# solenoid.net
KiCad netlist of a schematic drawn in EAGLE
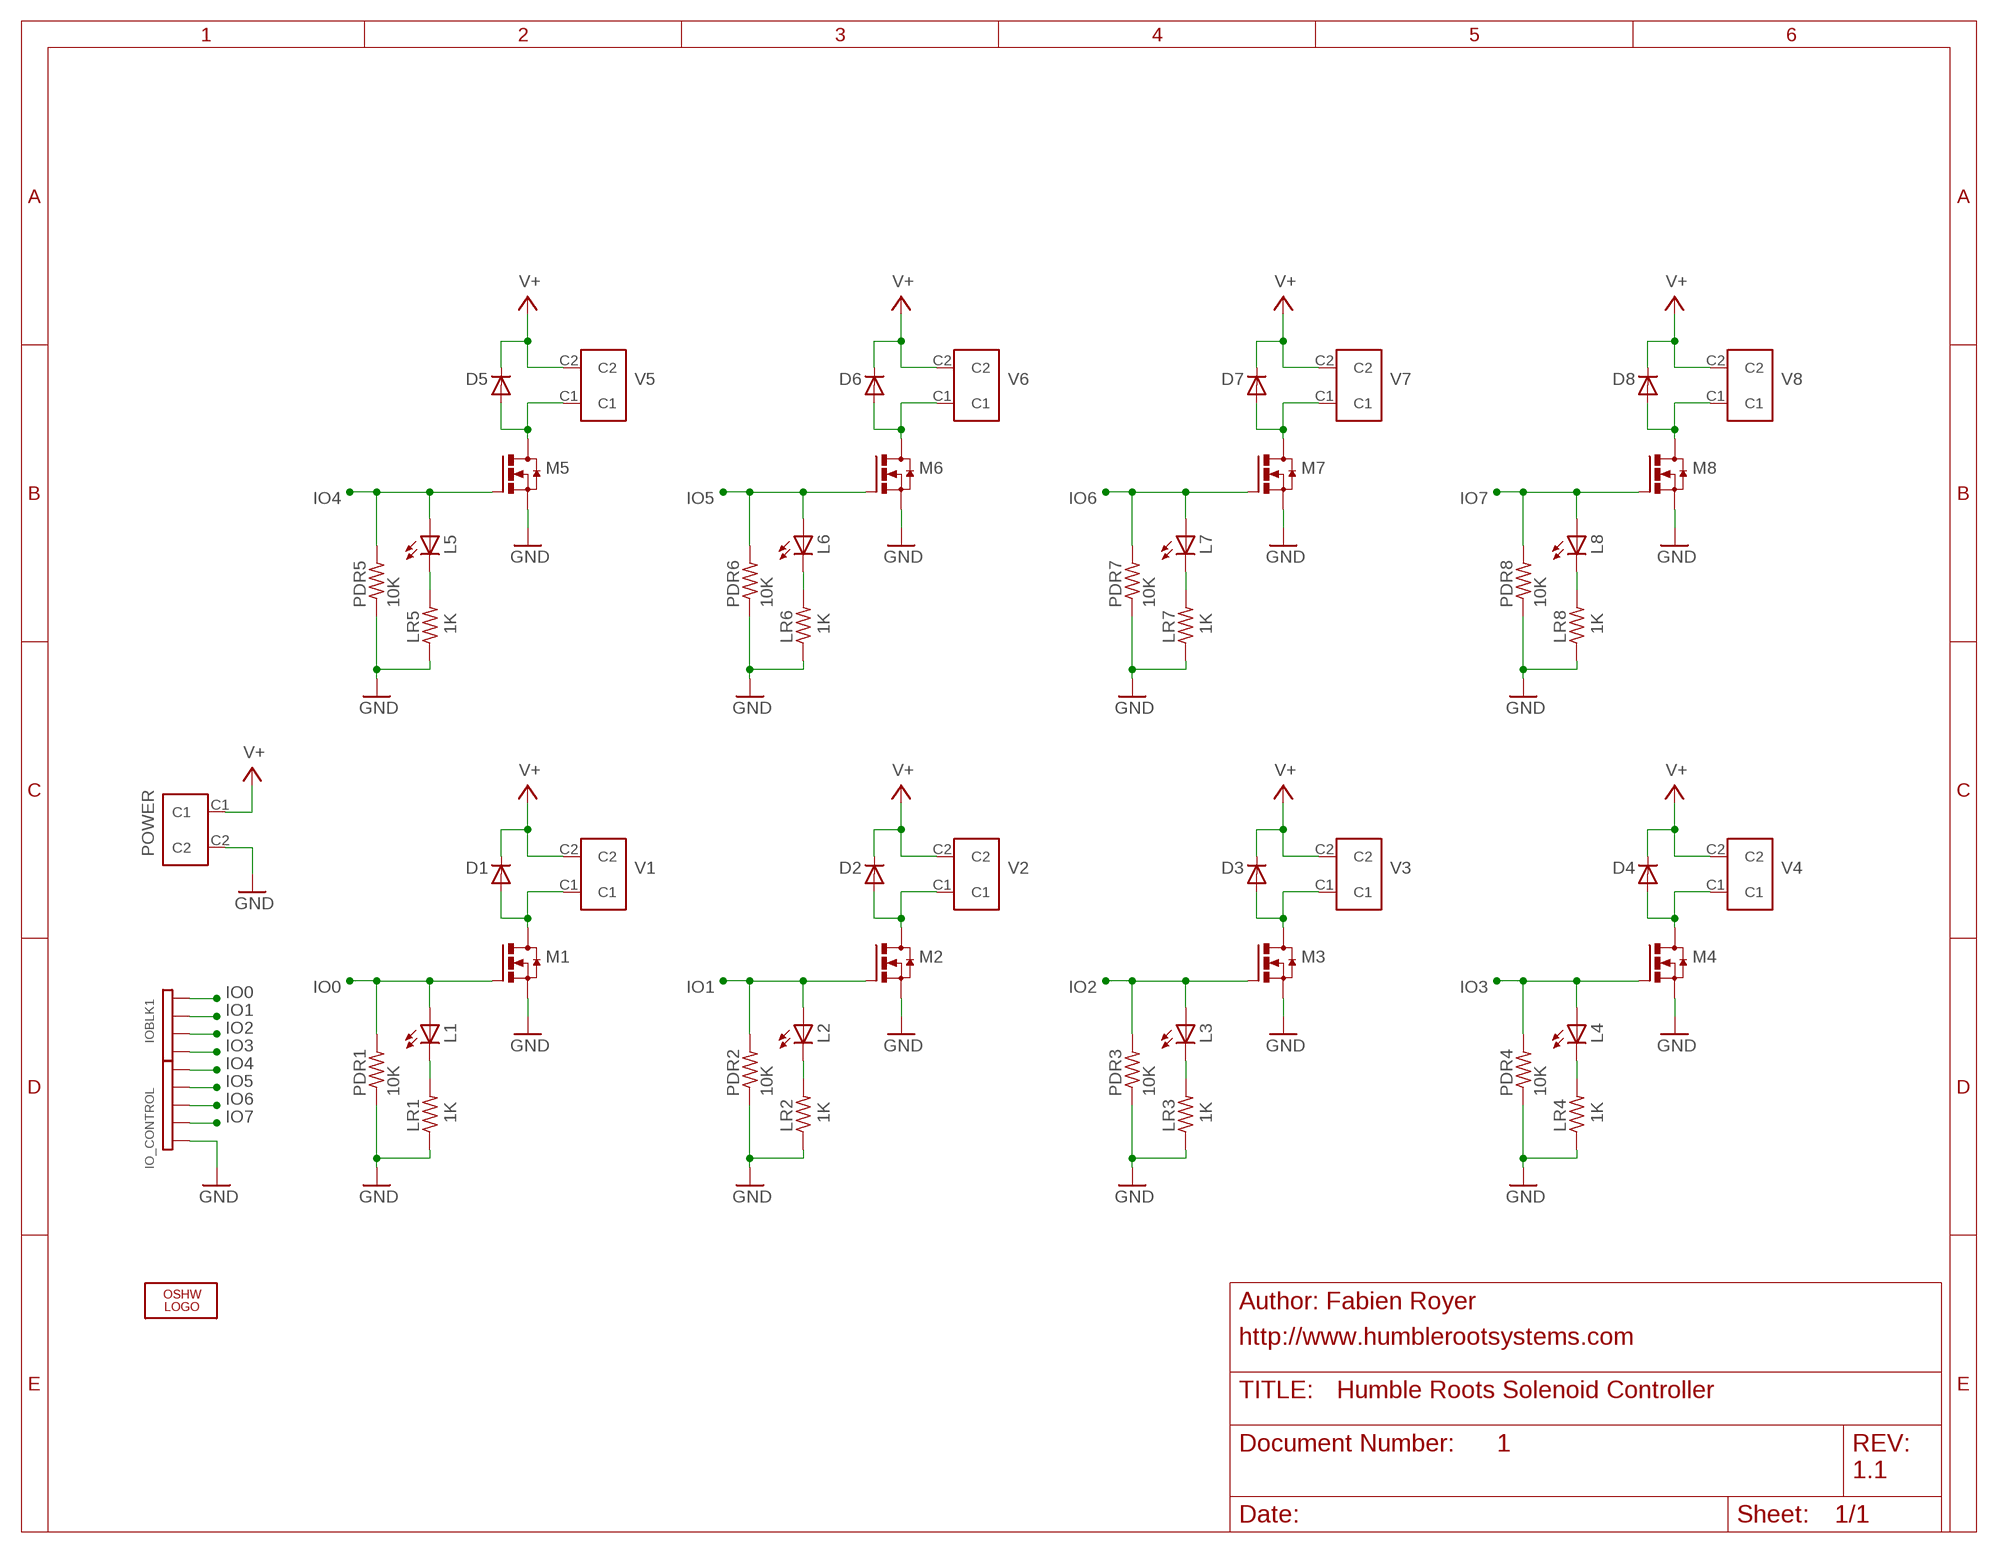
[diagram p0: schematic, sheet 1]

(export (version "E")
  (design (tool "Eeschema 10.0.6"))
  (components
    (comp (ref "D1")
      (value "1N4004")
      (footprint "eagle-import:DO41-10")
      (libsource (lib "eagle-import") (part "1N4004"))
    )
    (comp (ref "D2")
      (value "1N4004")
      (footprint "eagle-import:DO41-10")
      (libsource (lib "eagle-import") (part "1N4004"))
    )
    (comp (ref "D3")
      (value "1N4004")
      (footprint "eagle-import:DO41-10")
      (libsource (lib "eagle-import") (part "1N4004"))
    )
    (comp (ref "D4")
      (value "1N4004")
      (footprint "eagle-import:DO41-10")
      (libsource (lib "eagle-import") (part "1N4004"))
    )
    (comp (ref "D5")
      (value "1N4004")
      (footprint "eagle-import:DO41-10")
      (libsource (lib "eagle-import") (part "1N4004"))
    )
    (comp (ref "D6")
      (value "1N4004")
      (footprint "eagle-import:DO41-10")
      (libsource (lib "eagle-import") (part "1N4004"))
    )
    (comp (ref "D7")
      (value "1N4004")
      (footprint "eagle-import:DO41-10")
      (libsource (lib "eagle-import") (part "1N4004"))
    )
    (comp (ref "D8")
      (value "1N4004")
      (footprint "eagle-import:DO41-10")
      (libsource (lib "eagle-import") (part "1N4004"))
    )
    (comp (ref "IOBLK1")
      (value "PIN_HEADER_4_POSITIONS")
      (footprint "eagle-import:PIN_HEADER_4_POSITIONS")
      (libsource (lib "eagle-import") (part "PIN_HEADER_4_POSITIONS"))
    )
    (comp (ref "IO_CONTROL")
      (value "PIN_HEADER_5_POSITIONS")
      (footprint "eagle-import:PIN_HEADER_5_POSITIONS")
      (libsource (lib "eagle-import") (part "PIN_HEADER_5_POSITIONS"))
    )
    (comp (ref "L1")
      (value "2v 12mA")
      (footprint "eagle-import:LED3MM")
      (libsource (lib "eagle-import") (part "LED3MM"))
    )
    (comp (ref "L2")
      (value "2v 12mA")
      (footprint "eagle-import:LED3MM")
      (libsource (lib "eagle-import") (part "LED3MM"))
    )
    (comp (ref "L3")
      (value "2v 12mA")
      (footprint "eagle-import:LED3MM")
      (libsource (lib "eagle-import") (part "LED3MM"))
    )
    (comp (ref "L4")
      (value "2v 12mA")
      (footprint "eagle-import:LED3MM")
      (libsource (lib "eagle-import") (part "LED3MM"))
    )
    (comp (ref "L5")
      (value "2v 12mA")
      (footprint "eagle-import:LED3MM")
      (libsource (lib "eagle-import") (part "LED3MM"))
    )
    (comp (ref "L6")
      (value "2v 12mA")
      (footprint "eagle-import:LED3MM")
      (libsource (lib "eagle-import") (part "LED3MM"))
    )
    (comp (ref "L7")
      (value "2v 12mA")
      (footprint "eagle-import:LED3MM")
      (libsource (lib "eagle-import") (part "LED3MM"))
    )
    (comp (ref "L8")
      (value "2v 12mA")
      (footprint "eagle-import:LED3MM")
      (libsource (lib "eagle-import") (part "LED3MM"))
    )
    (comp (ref "LOGO1")
      (value "OSHW_LOGO_6MILX0200-NT")
      (footprint "eagle-import:OSHW_6X200_NOTEXT")
      (libsource (lib "eagle-import") (part "OSHW_LOGO_6MILX0200-NT"))
    )
    (comp (ref "LR1")
      (value "1K")
      (footprint "eagle-import:0207_10")
      (libsource (lib "eagle-import") (part "R-US_0207/10"))
    )
    (comp (ref "LR2")
      (value "1K")
      (footprint "eagle-import:0207_10")
      (libsource (lib "eagle-import") (part "R-US_0207/10"))
    )
    (comp (ref "LR3")
      (value "1K")
      (footprint "eagle-import:0207_10")
      (libsource (lib "eagle-import") (part "R-US_0207/10"))
    )
    (comp (ref "LR4")
      (value "1K")
      (footprint "eagle-import:0207_10")
      (libsource (lib "eagle-import") (part "R-US_0207/10"))
    )
    (comp (ref "LR5")
      (value "1K")
      (footprint "eagle-import:0207_10")
      (libsource (lib "eagle-import") (part "R-US_0207/10"))
    )
    (comp (ref "LR6")
      (value "1K")
      (footprint "eagle-import:0207_10")
      (libsource (lib "eagle-import") (part "R-US_0207/10"))
    )
    (comp (ref "LR7")
      (value "1K")
      (footprint "eagle-import:0207_10")
      (libsource (lib "eagle-import") (part "R-US_0207/10"))
    )
    (comp (ref "LR8")
      (value "1K")
      (footprint "eagle-import:0207_10")
      (libsource (lib "eagle-import") (part "R-US_0207/10"))
    )
    (comp (ref "M1")
      (value "INTERNATIONAL_RECTIFIER_IRLB8721PBF")
      (footprint "eagle-import:TO220ABS")
      (libsource (lib "eagle-import") (part "INTERNATIONAL_RECTIFIER_IRLB8721PBF"))
    )
    (comp (ref "M2")
      (value "INTERNATIONAL_RECTIFIER_IRLB8721PBF")
      (footprint "eagle-import:TO220ABS")
      (libsource (lib "eagle-import") (part "INTERNATIONAL_RECTIFIER_IRLB8721PBF"))
    )
    (comp (ref "M3")
      (value "INTERNATIONAL_RECTIFIER_IRLB8721PBF")
      (footprint "eagle-import:TO220ABS")
      (libsource (lib "eagle-import") (part "INTERNATIONAL_RECTIFIER_IRLB8721PBF"))
    )
    (comp (ref "M4")
      (value "INTERNATIONAL_RECTIFIER_IRLB8721PBF")
      (footprint "eagle-import:TO220ABS")
      (libsource (lib "eagle-import") (part "INTERNATIONAL_RECTIFIER_IRLB8721PBF"))
    )
    (comp (ref "M5")
      (value "INTERNATIONAL_RECTIFIER_IRLB8721PBF")
      (footprint "eagle-import:TO220ABS")
      (libsource (lib "eagle-import") (part "INTERNATIONAL_RECTIFIER_IRLB8721PBF"))
    )
    (comp (ref "M6")
      (value "INTERNATIONAL_RECTIFIER_IRLB8721PBF")
      (footprint "eagle-import:TO220ABS")
      (libsource (lib "eagle-import") (part "INTERNATIONAL_RECTIFIER_IRLB8721PBF"))
    )
    (comp (ref "M7")
      (value "INTERNATIONAL_RECTIFIER_IRLB8721PBF")
      (footprint "eagle-import:TO220ABS")
      (libsource (lib "eagle-import") (part "INTERNATIONAL_RECTIFIER_IRLB8721PBF"))
    )
    (comp (ref "M8")
      (value "INTERNATIONAL_RECTIFIER_IRLB8721PBF")
      (footprint "eagle-import:TO220ABS")
      (libsource (lib "eagle-import") (part "INTERNATIONAL_RECTIFIER_IRLB8721PBF"))
    )
    (comp (ref "PDR1")
      (value "10K")
      (footprint "eagle-import:0207_10")
      (libsource (lib "eagle-import") (part "R-US_0207/10"))
    )
    (comp (ref "PDR2")
      (value "10K")
      (footprint "eagle-import:0207_10")
      (libsource (lib "eagle-import") (part "R-US_0207/10"))
    )
    (comp (ref "PDR3")
      (value "10K")
      (footprint "eagle-import:0207_10")
      (libsource (lib "eagle-import") (part "R-US_0207/10"))
    )
    (comp (ref "PDR4")
      (value "10K")
      (footprint "eagle-import:0207_10")
      (libsource (lib "eagle-import") (part "R-US_0207/10"))
    )
    (comp (ref "PDR5")
      (value "10K")
      (footprint "eagle-import:0207_10")
      (libsource (lib "eagle-import") (part "R-US_0207/10"))
    )
    (comp (ref "PDR6")
      (value "10K")
      (footprint "eagle-import:0207_10")
      (libsource (lib "eagle-import") (part "R-US_0207/10"))
    )
    (comp (ref "PDR7")
      (value "10K")
      (footprint "eagle-import:0207_10")
      (libsource (lib "eagle-import") (part "R-US_0207/10"))
    )
    (comp (ref "PDR8")
      (value "10K")
      (footprint "eagle-import:0207_10")
      (libsource (lib "eagle-import") (part "R-US_0207/10"))
    )
    (comp (ref "POWER")
      (value "PHOENIX_WIRE_CONTACT_2_POSITIONS_GENERIC")
      (footprint "eagle-import:PHOENIX_WIRE_CONTACT_2_POSITIONS_GENERIC")
      (libsource (lib "eagle-import") (part "PHOENIX_WIRE_CONTACT_2_POSITIONS_GENERIC"))
    )
    (comp (ref "V1")
      (value "PHOENIX_WIRE_CONTACT_2_POSITIONS_GENERIC")
      (footprint "eagle-import:PHOENIX_WIRE_CONTACT_2_POSITIONS_GENERIC")
      (libsource (lib "eagle-import") (part "PHOENIX_WIRE_CONTACT_2_POSITIONS_GENERIC"))
    )
    (comp (ref "V2")
      (value "PHOENIX_WIRE_CONTACT_2_POSITIONS_GENERIC")
      (footprint "eagle-import:PHOENIX_WIRE_CONTACT_2_POSITIONS_GENERIC")
      (libsource (lib "eagle-import") (part "PHOENIX_WIRE_CONTACT_2_POSITIONS_GENERIC"))
    )
    (comp (ref "V3")
      (value "PHOENIX_WIRE_CONTACT_2_POSITIONS_GENERIC")
      (footprint "eagle-import:PHOENIX_WIRE_CONTACT_2_POSITIONS_GENERIC")
      (libsource (lib "eagle-import") (part "PHOENIX_WIRE_CONTACT_2_POSITIONS_GENERIC"))
    )
    (comp (ref "V4")
      (value "PHOENIX_WIRE_CONTACT_2_POSITIONS_GENERIC")
      (footprint "eagle-import:PHOENIX_WIRE_CONTACT_2_POSITIONS_GENERIC")
      (libsource (lib "eagle-import") (part "PHOENIX_WIRE_CONTACT_2_POSITIONS_GENERIC"))
    )
    (comp (ref "V5")
      (value "PHOENIX_WIRE_CONTACT_2_POSITIONS_GENERIC")
      (footprint "eagle-import:PHOENIX_WIRE_CONTACT_2_POSITIONS_GENERIC")
      (libsource (lib "eagle-import") (part "PHOENIX_WIRE_CONTACT_2_POSITIONS_GENERIC"))
    )
    (comp (ref "V6")
      (value "PHOENIX_WIRE_CONTACT_2_POSITIONS_GENERIC")
      (footprint "eagle-import:PHOENIX_WIRE_CONTACT_2_POSITIONS_GENERIC")
      (libsource (lib "eagle-import") (part "PHOENIX_WIRE_CONTACT_2_POSITIONS_GENERIC"))
    )
    (comp (ref "V7")
      (value "PHOENIX_WIRE_CONTACT_2_POSITIONS_GENERIC")
      (footprint "eagle-import:PHOENIX_WIRE_CONTACT_2_POSITIONS_GENERIC")
      (libsource (lib "eagle-import") (part "PHOENIX_WIRE_CONTACT_2_POSITIONS_GENERIC"))
    )
    (comp (ref "V8")
      (value "PHOENIX_WIRE_CONTACT_2_POSITIONS_GENERIC")
      (footprint "eagle-import:PHOENIX_WIRE_CONTACT_2_POSITIONS_GENERIC")
      (libsource (lib "eagle-import") (part "PHOENIX_WIRE_CONTACT_2_POSITIONS_GENERIC"))
    )
  )
  (nets
    (net (code "1") (name "/IO0") (class "Default")
      (node (ref "IOBLK1") (pin "1") (pinfunction "P$1_1") (pintype "bidirectional"))
      (node (ref "L1") (pin "A") (pinfunction "A_A") (pintype "passive"))
      (node (ref "M1") (pin "1") (pinfunction "GATE_1") (pintype "passive"))
      (node (ref "PDR1") (pin "2") (pinfunction "2_2") (pintype "passive"))
    )
    (net (code "2") (name "/IO1") (class "Default")
      (node (ref "IOBLK1") (pin "2") (pinfunction "P$2_2") (pintype "bidirectional"))
      (node (ref "L2") (pin "A") (pinfunction "A_A") (pintype "passive"))
      (node (ref "M2") (pin "1") (pinfunction "GATE_1") (pintype "passive"))
      (node (ref "PDR2") (pin "2") (pinfunction "2_2") (pintype "passive"))
    )
    (net (code "3") (name "/IO2") (class "Default")
      (node (ref "IOBLK1") (pin "3") (pinfunction "P$3_3") (pintype "bidirectional"))
      (node (ref "L3") (pin "A") (pinfunction "A_A") (pintype "passive"))
      (node (ref "M3") (pin "1") (pinfunction "GATE_1") (pintype "passive"))
      (node (ref "PDR3") (pin "2") (pinfunction "2_2") (pintype "passive"))
    )
    (net (code "4") (name "/IO3") (class "Default")
      (node (ref "IOBLK1") (pin "4") (pinfunction "P$4_4") (pintype "bidirectional"))
      (node (ref "L4") (pin "A") (pinfunction "A_A") (pintype "passive"))
      (node (ref "M4") (pin "1") (pinfunction "GATE_1") (pintype "passive"))
      (node (ref "PDR4") (pin "2") (pinfunction "2_2") (pintype "passive"))
    )
    (net (code "5") (name "/IO4") (class "Default")
      (node (ref "IO_CONTROL") (pin "1") (pinfunction "P$1_1") (pintype "bidirectional"))
      (node (ref "L5") (pin "A") (pinfunction "A_A") (pintype "passive"))
      (node (ref "M5") (pin "1") (pinfunction "GATE_1") (pintype "passive"))
      (node (ref "PDR5") (pin "2") (pinfunction "2_2") (pintype "passive"))
    )
    (net (code "6") (name "/IO5") (class "Default")
      (node (ref "IO_CONTROL") (pin "2") (pinfunction "P$2_2") (pintype "bidirectional"))
      (node (ref "L6") (pin "A") (pinfunction "A_A") (pintype "passive"))
      (node (ref "M6") (pin "1") (pinfunction "GATE_1") (pintype "passive"))
      (node (ref "PDR6") (pin "2") (pinfunction "2_2") (pintype "passive"))
    )
    (net (code "7") (name "/IO6") (class "Default")
      (node (ref "IO_CONTROL") (pin "3") (pinfunction "P$3_3") (pintype "bidirectional"))
      (node (ref "L7") (pin "A") (pinfunction "A_A") (pintype "passive"))
      (node (ref "M7") (pin "1") (pinfunction "GATE_1") (pintype "passive"))
      (node (ref "PDR7") (pin "2") (pinfunction "2_2") (pintype "passive"))
    )
    (net (code "8") (name "/IO7") (class "Default")
      (node (ref "IO_CONTROL") (pin "4") (pinfunction "P$4_4") (pintype "bidirectional"))
      (node (ref "L8") (pin "A") (pinfunction "A_A") (pintype "passive"))
      (node (ref "M8") (pin "1") (pinfunction "GATE_1") (pintype "passive"))
      (node (ref "PDR8") (pin "2") (pinfunction "2_2") (pintype "passive"))
    )
    (net (code "9") (name "GND") (class "Default")
      (node (ref "IO_CONTROL") (pin "5") (pinfunction "P$5_5") (pintype "bidirectional"))
      (node (ref "LR1") (pin "1") (pinfunction "1_1") (pintype "passive"))
      (node (ref "LR2") (pin "1") (pinfunction "1_1") (pintype "passive"))
      (node (ref "LR3") (pin "1") (pinfunction "1_1") (pintype "passive"))
      (node (ref "LR4") (pin "1") (pinfunction "1_1") (pintype "passive"))
      (node (ref "LR5") (pin "1") (pinfunction "1_1") (pintype "passive"))
      (node (ref "LR6") (pin "1") (pinfunction "1_1") (pintype "passive"))
      (node (ref "LR7") (pin "1") (pinfunction "1_1") (pintype "passive"))
      (node (ref "LR8") (pin "1") (pinfunction "1_1") (pintype "passive"))
      (node (ref "M1") (pin "3") (pinfunction "SOURCE_3") (pintype "passive"))
      (node (ref "M2") (pin "3") (pinfunction "SOURCE_3") (pintype "passive"))
      (node (ref "M3") (pin "3") (pinfunction "SOURCE_3") (pintype "passive"))
      (node (ref "M4") (pin "3") (pinfunction "SOURCE_3") (pintype "passive"))
      (node (ref "M5") (pin "3") (pinfunction "SOURCE_3") (pintype "passive"))
      (node (ref "M6") (pin "3") (pinfunction "SOURCE_3") (pintype "passive"))
      (node (ref "M7") (pin "3") (pinfunction "SOURCE_3") (pintype "passive"))
      (node (ref "M8") (pin "3") (pinfunction "SOURCE_3") (pintype "passive"))
      (node (ref "PDR1") (pin "1") (pinfunction "1_1") (pintype "passive"))
      (node (ref "PDR2") (pin "1") (pinfunction "1_1") (pintype "passive"))
      (node (ref "PDR3") (pin "1") (pinfunction "1_1") (pintype "passive"))
      (node (ref "PDR4") (pin "1") (pinfunction "1_1") (pintype "passive"))
      (node (ref "PDR5") (pin "1") (pinfunction "1_1") (pintype "passive"))
      (node (ref "PDR6") (pin "1") (pinfunction "1_1") (pintype "passive"))
      (node (ref "PDR7") (pin "1") (pinfunction "1_1") (pintype "passive"))
      (node (ref "PDR8") (pin "1") (pinfunction "1_1") (pintype "passive"))
      (node (ref "POWER") (pin "C2") (pinfunction "C2_C2") (pintype "passive"))
    )
    (net (code "10") (name "Net-(L1-C)") (class "Default")
      (node (ref "L1") (pin "K") (pinfunction "C_K") (pintype "passive"))
      (node (ref "LR1") (pin "2") (pinfunction "2_2") (pintype "passive"))
    )
    (net (code "11") (name "Net-(L2-C)") (class "Default")
      (node (ref "L2") (pin "K") (pinfunction "C_K") (pintype "passive"))
      (node (ref "LR2") (pin "2") (pinfunction "2_2") (pintype "passive"))
    )
    (net (code "12") (name "Net-(L3-C)") (class "Default")
      (node (ref "L3") (pin "K") (pinfunction "C_K") (pintype "passive"))
      (node (ref "LR3") (pin "2") (pinfunction "2_2") (pintype "passive"))
    )
    (net (code "13") (name "Net-(L4-C)") (class "Default")
      (node (ref "L4") (pin "K") (pinfunction "C_K") (pintype "passive"))
      (node (ref "LR4") (pin "2") (pinfunction "2_2") (pintype "passive"))
    )
    (net (code "14") (name "Net-(L5-C)") (class "Default")
      (node (ref "L5") (pin "K") (pinfunction "C_K") (pintype "passive"))
      (node (ref "LR5") (pin "2") (pinfunction "2_2") (pintype "passive"))
    )
    (net (code "15") (name "Net-(L6-C)") (class "Default")
      (node (ref "L6") (pin "K") (pinfunction "C_K") (pintype "passive"))
      (node (ref "LR6") (pin "2") (pinfunction "2_2") (pintype "passive"))
    )
    (net (code "16") (name "Net-(L7-C)") (class "Default")
      (node (ref "L7") (pin "K") (pinfunction "C_K") (pintype "passive"))
      (node (ref "LR7") (pin "2") (pinfunction "2_2") (pintype "passive"))
    )
    (net (code "17") (name "Net-(L8-C)") (class "Default")
      (node (ref "L8") (pin "K") (pinfunction "C_K") (pintype "passive"))
      (node (ref "LR8") (pin "2") (pinfunction "2_2") (pintype "passive"))
    )
    (net (code "18") (name "Net-(M1-DRAIN)") (class "Default")
      (node (ref "D1") (pin "A") (pinfunction "A_A") (pintype "passive"))
      (node (ref "M1") (pin "2") (pinfunction "DRAIN_2") (pintype "passive"))
      (node (ref "V1") (pin "C1") (pinfunction "C1_C1") (pintype "passive"))
    )
    (net (code "19") (name "Net-(M2-DRAIN)") (class "Default")
      (node (ref "D2") (pin "A") (pinfunction "A_A") (pintype "passive"))
      (node (ref "M2") (pin "2") (pinfunction "DRAIN_2") (pintype "passive"))
      (node (ref "V2") (pin "C1") (pinfunction "C1_C1") (pintype "passive"))
    )
    (net (code "20") (name "Net-(M3-DRAIN)") (class "Default")
      (node (ref "D3") (pin "A") (pinfunction "A_A") (pintype "passive"))
      (node (ref "M3") (pin "2") (pinfunction "DRAIN_2") (pintype "passive"))
      (node (ref "V3") (pin "C1") (pinfunction "C1_C1") (pintype "passive"))
    )
    (net (code "21") (name "Net-(M4-DRAIN)") (class "Default")
      (node (ref "D4") (pin "A") (pinfunction "A_A") (pintype "passive"))
      (node (ref "M4") (pin "2") (pinfunction "DRAIN_2") (pintype "passive"))
      (node (ref "V4") (pin "C1") (pinfunction "C1_C1") (pintype "passive"))
    )
    (net (code "22") (name "Net-(M5-DRAIN)") (class "Default")
      (node (ref "D5") (pin "A") (pinfunction "A_A") (pintype "passive"))
      (node (ref "M5") (pin "2") (pinfunction "DRAIN_2") (pintype "passive"))
      (node (ref "V5") (pin "C1") (pinfunction "C1_C1") (pintype "passive"))
    )
    (net (code "23") (name "Net-(M6-DRAIN)") (class "Default")
      (node (ref "D6") (pin "A") (pinfunction "A_A") (pintype "passive"))
      (node (ref "M6") (pin "2") (pinfunction "DRAIN_2") (pintype "passive"))
      (node (ref "V6") (pin "C1") (pinfunction "C1_C1") (pintype "passive"))
    )
    (net (code "24") (name "Net-(M7-DRAIN)") (class "Default")
      (node (ref "D7") (pin "A") (pinfunction "A_A") (pintype "passive"))
      (node (ref "M7") (pin "2") (pinfunction "DRAIN_2") (pintype "passive"))
      (node (ref "V7") (pin "C1") (pinfunction "C1_C1") (pintype "passive"))
    )
    (net (code "25") (name "Net-(M8-DRAIN)") (class "Default")
      (node (ref "D8") (pin "A") (pinfunction "A_A") (pintype "passive"))
      (node (ref "M8") (pin "2") (pinfunction "DRAIN_2") (pintype "passive"))
      (node (ref "V8") (pin "C1") (pinfunction "C1_C1") (pintype "passive"))
    )
    (net (code "26") (name "V+") (class "Default")
      (node (ref "D1") (pin "C") (pinfunction "C_C") (pintype "passive"))
      (node (ref "D2") (pin "C") (pinfunction "C_C") (pintype "passive"))
      (node (ref "D3") (pin "C") (pinfunction "C_C") (pintype "passive"))
      (node (ref "D4") (pin "C") (pinfunction "C_C") (pintype "passive"))
      (node (ref "D5") (pin "C") (pinfunction "C_C") (pintype "passive"))
      (node (ref "D6") (pin "C") (pinfunction "C_C") (pintype "passive"))
      (node (ref "D7") (pin "C") (pinfunction "C_C") (pintype "passive"))
      (node (ref "D8") (pin "C") (pinfunction "C_C") (pintype "passive"))
      (node (ref "POWER") (pin "C1") (pinfunction "C1_C1") (pintype "passive"))
      (node (ref "V1") (pin "C2") (pinfunction "C2_C2") (pintype "passive"))
      (node (ref "V2") (pin "C2") (pinfunction "C2_C2") (pintype "passive"))
      (node (ref "V3") (pin "C2") (pinfunction "C2_C2") (pintype "passive"))
      (node (ref "V4") (pin "C2") (pinfunction "C2_C2") (pintype "passive"))
      (node (ref "V5") (pin "C2") (pinfunction "C2_C2") (pintype "passive"))
      (node (ref "V6") (pin "C2") (pinfunction "C2_C2") (pintype "passive"))
      (node (ref "V7") (pin "C2") (pinfunction "C2_C2") (pintype "passive"))
      (node (ref "V8") (pin "C2") (pinfunction "C2_C2") (pintype "passive"))
    )
  )
)
